# front_panel.net
KiCad netlist of a schematic drawn in EAGLE
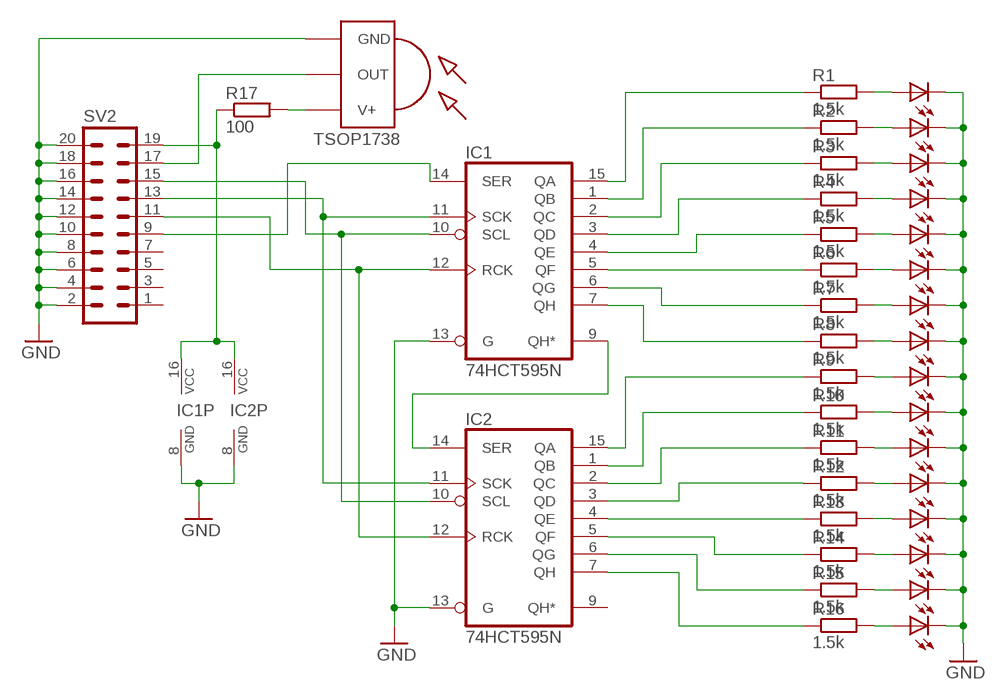
[diagram p0: schematic, sheet 1]

(export (version "E")
  (design (tool "Eeschema 10.0.6"))
  (components
    (comp (ref "IC1")
      (value "74HCT595N")
      (footprint "eagle-import:DIL16")
      (libsource (lib "eagle-import") (part "74595NHCT"))
    )
    (comp (ref "IC2")
      (value "74HCT595N")
      (footprint "eagle-import:DIL16")
      (libsource (lib "eagle-import") (part "74595NHCT"))
    )
    (comp (ref "R1")
      (value "1.5k")
      (footprint "eagle-import:0207_7")
      (libsource (lib "eagle-import") (part "R-EU_0207/7"))
    )
    (comp (ref "R2")
      (value "1.5k")
      (footprint "eagle-import:0207_7")
      (libsource (lib "eagle-import") (part "R-EU_0207/7"))
    )
    (comp (ref "R3")
      (value "1.5k")
      (footprint "eagle-import:0207_7")
      (libsource (lib "eagle-import") (part "R-EU_0207/7"))
    )
    (comp (ref "R4")
      (value "1.5k")
      (footprint "eagle-import:0207_7")
      (libsource (lib "eagle-import") (part "R-EU_0207/7"))
    )
    (comp (ref "R5")
      (value "1.5k")
      (footprint "eagle-import:0207_7")
      (libsource (lib "eagle-import") (part "R-EU_0207/7"))
    )
    (comp (ref "R6")
      (value "1.5k")
      (footprint "eagle-import:0207_7")
      (libsource (lib "eagle-import") (part "R-EU_0207/7"))
    )
    (comp (ref "R7")
      (value "1.5k")
      (footprint "eagle-import:0207_7")
      (libsource (lib "eagle-import") (part "R-EU_0207/7"))
    )
    (comp (ref "R8")
      (value "1.5k")
      (footprint "eagle-import:0207_7")
      (libsource (lib "eagle-import") (part "R-EU_0207/7"))
    )
    (comp (ref "R9")
      (value "1.5k")
      (footprint "eagle-import:0207_7")
      (libsource (lib "eagle-import") (part "R-EU_0207/7"))
    )
    (comp (ref "R10")
      (value "1.5k")
      (footprint "eagle-import:0207_7")
      (libsource (lib "eagle-import") (part "R-EU_0207/7"))
    )
    (comp (ref "R11")
      (value "1.5k")
      (footprint "eagle-import:0207_7")
      (libsource (lib "eagle-import") (part "R-EU_0207/7"))
    )
    (comp (ref "R12")
      (value "1.5k")
      (footprint "eagle-import:0207_7")
      (libsource (lib "eagle-import") (part "R-EU_0207/7"))
    )
    (comp (ref "R13")
      (value "1.5k")
      (footprint "eagle-import:0207_7")
      (libsource (lib "eagle-import") (part "R-EU_0207/7"))
    )
    (comp (ref "R14")
      (value "1.5k")
      (footprint "eagle-import:0207_7")
      (libsource (lib "eagle-import") (part "R-EU_0207/7"))
    )
    (comp (ref "R15")
      (value "1.5k")
      (footprint "eagle-import:0207_7")
      (libsource (lib "eagle-import") (part "R-EU_0207/7"))
    )
    (comp (ref "R16")
      (value "1.5k")
      (footprint "eagle-import:0207_7")
      (libsource (lib "eagle-import") (part "R-EU_0207/7"))
    )
    (comp (ref "R17")
      (value "100")
      (footprint "eagle-import:0207_7")
      (libsource (lib "eagle-import") (part "R-EU_0207/7"))
    )
    (comp (ref "SV2")
      (value "MA10-2")
      (footprint "eagle-import:MA10-2")
      (libsource (lib "eagle-import") (part "MA10-2"))
    )
    (comp (ref "U$2")
      (value "LED_RING_16")
      (footprint "eagle-import:POTI_LED_RING16")
      (libsource (lib "eagle-import") (part "LED_RING_16"))
    )
    (comp (ref "U$3")
      (value "TSOP1738")
      (footprint "eagle-import:TSOP17XX")
      (libsource (lib "eagle-import") (part "TSOP1738"))
    )
  )
  (nets
    (net (code "1") (name "GND") (class "Default")
      (node (ref "IC1") (pin "13") (pinfunction "G_13") (pintype "input"))
      (node (ref "IC1") (pin "8") (pinfunction "GND_8") (pintype "power_in"))
      (node (ref "IC2") (pin "13") (pinfunction "G_13") (pintype "input"))
      (node (ref "IC2") (pin "8") (pinfunction "GND_8") (pintype "power_in"))
      (node (ref "SV2") (pin "10") (pinfunction "10_10") (pintype "passive"))
      (node (ref "SV2") (pin "12") (pinfunction "12_12") (pintype "passive"))
      (node (ref "SV2") (pin "14") (pinfunction "14_14") (pintype "passive"))
      (node (ref "SV2") (pin "16") (pinfunction "16_16") (pintype "passive"))
      (node (ref "SV2") (pin "18") (pinfunction "18_18") (pintype "passive"))
      (node (ref "SV2") (pin "2") (pinfunction "2_2") (pintype "passive"))
      (node (ref "SV2") (pin "20") (pinfunction "20_20") (pintype "passive"))
      (node (ref "SV2") (pin "4") (pinfunction "4_4") (pintype "passive"))
      (node (ref "SV2") (pin "6") (pinfunction "6_6") (pintype "passive"))
      (node (ref "SV2") (pin "8") (pinfunction "8_8") (pintype "passive"))
      (node (ref "U$2") (pin "K0") (pinfunction "K0_K0") (pintype "passive"))
      (node (ref "U$2") (pin "K1") (pinfunction "K1_K1") (pintype "passive"))
      (node (ref "U$2") (pin "K10") (pinfunction "K10_K10") (pintype "passive"))
      (node (ref "U$2") (pin "K11") (pinfunction "K11_K11") (pintype "passive"))
      (node (ref "U$2") (pin "K12") (pinfunction "K12_K12") (pintype "passive"))
      (node (ref "U$2") (pin "K13") (pinfunction "K13_K13") (pintype "passive"))
      (node (ref "U$2") (pin "K14") (pinfunction "K14_K14") (pintype "passive"))
      (node (ref "U$2") (pin "K15") (pinfunction "K15_K15") (pintype "passive"))
      (node (ref "U$2") (pin "K2") (pinfunction "K2_K2") (pintype "passive"))
      (node (ref "U$2") (pin "K3") (pinfunction "K3_K3") (pintype "passive"))
      (node (ref "U$2") (pin "K4") (pinfunction "K4_K4") (pintype "passive"))
      (node (ref "U$2") (pin "K5") (pinfunction "K5_K5") (pintype "passive"))
      (node (ref "U$2") (pin "K6") (pinfunction "K6_K6") (pintype "passive"))
      (node (ref "U$2") (pin "K7") (pinfunction "K7_K7") (pintype "passive"))
      (node (ref "U$2") (pin "K8") (pinfunction "K8_K8") (pintype "passive"))
      (node (ref "U$2") (pin "K9") (pinfunction "K9_K9") (pintype "passive"))
      (node (ref "U$3") (pin "GND") (pinfunction "GND_GND") (pintype "bidirectional"))
    )
    (net (code "2") (name "Net-(IC1A-QA)") (class "Default")
      (node (ref "IC1") (pin "15") (pinfunction "QA_15") (pintype "tri_state"))
      (node (ref "R1") (pin "1") (pinfunction "1_1") (pintype "passive"))
    )
    (net (code "3") (name "Net-(IC1A-QB)") (class "Default")
      (node (ref "IC1") (pin "1") (pinfunction "QB_1") (pintype "tri_state"))
      (node (ref "R2") (pin "1") (pinfunction "1_1") (pintype "passive"))
    )
    (net (code "4") (name "Net-(IC1A-QC)") (class "Default")
      (node (ref "IC1") (pin "2") (pinfunction "QC_2") (pintype "tri_state"))
      (node (ref "R3") (pin "1") (pinfunction "1_1") (pintype "passive"))
    )
    (net (code "5") (name "Net-(IC1A-QD)") (class "Default")
      (node (ref "IC1") (pin "3") (pinfunction "QD_3") (pintype "tri_state"))
      (node (ref "R4") (pin "1") (pinfunction "1_1") (pintype "passive"))
    )
    (net (code "6") (name "Net-(IC1A-QE)") (class "Default")
      (node (ref "IC1") (pin "4") (pinfunction "QE_4") (pintype "tri_state"))
      (node (ref "R5") (pin "1") (pinfunction "1_1") (pintype "passive"))
    )
    (net (code "7") (name "Net-(IC1A-QF)") (class "Default")
      (node (ref "IC1") (pin "5") (pinfunction "QF_5") (pintype "tri_state"))
      (node (ref "R6") (pin "1") (pinfunction "1_1") (pintype "passive"))
    )
    (net (code "8") (name "Net-(IC1A-QG)") (class "Default")
      (node (ref "IC1") (pin "6") (pinfunction "QG_6") (pintype "tri_state"))
      (node (ref "R7") (pin "1") (pinfunction "1_1") (pintype "passive"))
    )
    (net (code "9") (name "Net-(IC1A-QH)") (class "Default")
      (node (ref "IC1") (pin "7") (pinfunction "QH_7") (pintype "tri_state"))
      (node (ref "R8") (pin "1") (pinfunction "1_1") (pintype "passive"))
    )
    (net (code "10") (name "Net-(IC1A-QH*)") (class "Default")
      (node (ref "IC1") (pin "9") (pinfunction "QH*_9") (pintype "tri_state"))
      (node (ref "IC2") (pin "14") (pinfunction "SER_14") (pintype "input"))
    )
    (net (code "11") (name "Net-(IC1A-RCK)") (class "Default")
      (node (ref "IC1") (pin "12") (pinfunction "RCK_12") (pintype "input"))
      (node (ref "IC2") (pin "12") (pinfunction "RCK_12") (pintype "input"))
      (node (ref "SV2") (pin "11") (pinfunction "11_11") (pintype "passive"))
    )
    (net (code "12") (name "Net-(IC1A-SCK)") (class "Default")
      (node (ref "IC1") (pin "11") (pinfunction "SCK_11") (pintype "input"))
      (node (ref "IC2") (pin "11") (pinfunction "SCK_11") (pintype "input"))
      (node (ref "SV2") (pin "13") (pinfunction "13_13") (pintype "passive"))
    )
    (net (code "13") (name "Net-(IC1A-SCL)") (class "Default")
      (node (ref "IC1") (pin "10") (pinfunction "SCL_10") (pintype "input"))
      (node (ref "IC2") (pin "10") (pinfunction "SCL_10") (pintype "input"))
      (node (ref "SV2") (pin "15") (pinfunction "15_15") (pintype "passive"))
    )
    (net (code "14") (name "Net-(IC1A-SER)") (class "Default")
      (node (ref "IC1") (pin "14") (pinfunction "SER_14") (pintype "input"))
      (node (ref "SV2") (pin "9") (pinfunction "9_9") (pintype "passive"))
    )
    (net (code "15") (name "Net-(IC1B-VCC)") (class "Default")
      (node (ref "IC1") (pin "16") (pinfunction "VCC_16") (pintype "power_in"))
      (node (ref "IC2") (pin "16") (pinfunction "VCC_16") (pintype "power_in"))
      (node (ref "R17") (pin "1") (pinfunction "1_1") (pintype "passive"))
      (node (ref "SV2") (pin "19") (pinfunction "19_19") (pintype "passive"))
    )
    (net (code "16") (name "Net-(IC2A-QA)") (class "Default")
      (node (ref "IC2") (pin "15") (pinfunction "QA_15") (pintype "tri_state"))
      (node (ref "R9") (pin "1") (pinfunction "1_1") (pintype "passive"))
    )
    (net (code "17") (name "Net-(IC2A-QB)") (class "Default")
      (node (ref "IC2") (pin "1") (pinfunction "QB_1") (pintype "tri_state"))
      (node (ref "R10") (pin "1") (pinfunction "1_1") (pintype "passive"))
    )
    (net (code "18") (name "Net-(IC2A-QC)") (class "Default")
      (node (ref "IC2") (pin "2") (pinfunction "QC_2") (pintype "tri_state"))
      (node (ref "R11") (pin "1") (pinfunction "1_1") (pintype "passive"))
    )
    (net (code "19") (name "Net-(IC2A-QD)") (class "Default")
      (node (ref "IC2") (pin "3") (pinfunction "QD_3") (pintype "tri_state"))
      (node (ref "R12") (pin "1") (pinfunction "1_1") (pintype "passive"))
    )
    (net (code "20") (name "Net-(IC2A-QE)") (class "Default")
      (node (ref "IC2") (pin "4") (pinfunction "QE_4") (pintype "tri_state"))
      (node (ref "R13") (pin "1") (pinfunction "1_1") (pintype "passive"))
    )
    (net (code "21") (name "Net-(IC2A-QF)") (class "Default")
      (node (ref "IC2") (pin "5") (pinfunction "QF_5") (pintype "tri_state"))
      (node (ref "R14") (pin "1") (pinfunction "1_1") (pintype "passive"))
    )
    (net (code "22") (name "Net-(IC2A-QG)") (class "Default")
      (node (ref "IC2") (pin "6") (pinfunction "QG_6") (pintype "tri_state"))
      (node (ref "R15") (pin "1") (pinfunction "1_1") (pintype "passive"))
    )
    (net (code "23") (name "Net-(IC2A-QH)") (class "Default")
      (node (ref "IC2") (pin "7") (pinfunction "QH_7") (pintype "tri_state"))
      (node (ref "R16") (pin "1") (pinfunction "1_1") (pintype "passive"))
    )
    (net (code "24") (name "Net-(R1-Pad2)") (class "Default")
      (node (ref "R1") (pin "2") (pinfunction "2_2") (pintype "passive"))
      (node (ref "U$2") (pin "A0") (pinfunction "A0_A0") (pintype "passive"))
    )
    (net (code "25") (name "Net-(R2-Pad2)") (class "Default")
      (node (ref "R2") (pin "2") (pinfunction "2_2") (pintype "passive"))
      (node (ref "U$2") (pin "A1") (pinfunction "A1_A1") (pintype "passive"))
    )
    (net (code "26") (name "Net-(R3-Pad2)") (class "Default")
      (node (ref "R3") (pin "2") (pinfunction "2_2") (pintype "passive"))
      (node (ref "U$2") (pin "A2") (pinfunction "A2_A2") (pintype "passive"))
    )
    (net (code "27") (name "Net-(R4-Pad2)") (class "Default")
      (node (ref "R4") (pin "2") (pinfunction "2_2") (pintype "passive"))
      (node (ref "U$2") (pin "A3") (pinfunction "A3_A3") (pintype "passive"))
    )
    (net (code "28") (name "Net-(R5-Pad2)") (class "Default")
      (node (ref "R5") (pin "2") (pinfunction "2_2") (pintype "passive"))
      (node (ref "U$2") (pin "A4") (pinfunction "A4_A4") (pintype "passive"))
    )
    (net (code "29") (name "Net-(R6-Pad2)") (class "Default")
      (node (ref "R6") (pin "2") (pinfunction "2_2") (pintype "passive"))
      (node (ref "U$2") (pin "A5") (pinfunction "A5_A5") (pintype "passive"))
    )
    (net (code "30") (name "Net-(R7-Pad2)") (class "Default")
      (node (ref "R7") (pin "2") (pinfunction "2_2") (pintype "passive"))
      (node (ref "U$2") (pin "A6") (pinfunction "A6_A6") (pintype "passive"))
    )
    (net (code "31") (name "Net-(R8-Pad2)") (class "Default")
      (node (ref "R8") (pin "2") (pinfunction "2_2") (pintype "passive"))
      (node (ref "U$2") (pin "A7") (pinfunction "A7_A7") (pintype "passive"))
    )
    (net (code "32") (name "Net-(R9-Pad2)") (class "Default")
      (node (ref "R9") (pin "2") (pinfunction "2_2") (pintype "passive"))
      (node (ref "U$2") (pin "A8") (pinfunction "A8_A8") (pintype "passive"))
    )
    (net (code "33") (name "Net-(R10-Pad2)") (class "Default")
      (node (ref "R10") (pin "2") (pinfunction "2_2") (pintype "passive"))
      (node (ref "U$2") (pin "A9") (pinfunction "A9_A9") (pintype "passive"))
    )
    (net (code "34") (name "Net-(R11-Pad2)") (class "Default")
      (node (ref "R11") (pin "2") (pinfunction "2_2") (pintype "passive"))
      (node (ref "U$2") (pin "A10") (pinfunction "A10_A10") (pintype "passive"))
    )
    (net (code "35") (name "Net-(R12-Pad2)") (class "Default")
      (node (ref "R12") (pin "2") (pinfunction "2_2") (pintype "passive"))
      (node (ref "U$2") (pin "A11") (pinfunction "A11_A11") (pintype "passive"))
    )
    (net (code "36") (name "Net-(R13-Pad2)") (class "Default")
      (node (ref "R13") (pin "2") (pinfunction "2_2") (pintype "passive"))
      (node (ref "U$2") (pin "A12") (pinfunction "A12_A12") (pintype "passive"))
    )
    (net (code "37") (name "Net-(R14-Pad2)") (class "Default")
      (node (ref "R14") (pin "2") (pinfunction "2_2") (pintype "passive"))
      (node (ref "U$2") (pin "A13") (pinfunction "A13_A13") (pintype "passive"))
    )
    (net (code "38") (name "Net-(R15-Pad2)") (class "Default")
      (node (ref "R15") (pin "2") (pinfunction "2_2") (pintype "passive"))
      (node (ref "U$2") (pin "A14") (pinfunction "A14_A14") (pintype "passive"))
    )
    (net (code "39") (name "Net-(R16-Pad2)") (class "Default")
      (node (ref "R16") (pin "2") (pinfunction "2_2") (pintype "passive"))
      (node (ref "U$2") (pin "A15") (pinfunction "A15_A15") (pintype "passive"))
    )
    (net (code "40") (name "Net-(R17-Pad2)") (class "Default")
      (node (ref "R17") (pin "2") (pinfunction "2_2") (pintype "passive"))
      (node (ref "U$3") (pin "V+") (pinfunction "V+_V+") (pintype "bidirectional"))
    )
    (net (code "41") (name "Net-(SV2-Pad17)") (class "Default")
      (node (ref "SV2") (pin "17") (pinfunction "17_17") (pintype "passive"))
      (node (ref "U$3") (pin "OUT") (pinfunction "OUT_OUT") (pintype "bidirectional"))
    )
    (net (code "42") (name "unconnected-(IC2A-QH*-Pad9)") (class "Default")
      (node (ref "IC2") (pin "9") (pinfunction "QH*_9") (pintype "tri_state"))
    )
    (net (code "43") (name "unconnected-(SV2-Pad1)") (class "Default")
      (node (ref "SV2") (pin "1") (pinfunction "1_1") (pintype "passive"))
    )
    (net (code "44") (name "unconnected-(SV2-Pad3)") (class "Default")
      (node (ref "SV2") (pin "3") (pinfunction "3_3") (pintype "passive"))
    )
    (net (code "45") (name "unconnected-(SV2-Pad5)") (class "Default")
      (node (ref "SV2") (pin "5") (pinfunction "5_5") (pintype "passive"))
    )
    (net (code "46") (name "unconnected-(SV2-Pad7)") (class "Default")
      (node (ref "SV2") (pin "7") (pinfunction "7_7") (pintype "passive"))
    )
  )
)
